# oscyloskop-0v2.net
KiCad netlist of a schematic drawn in EAGLE
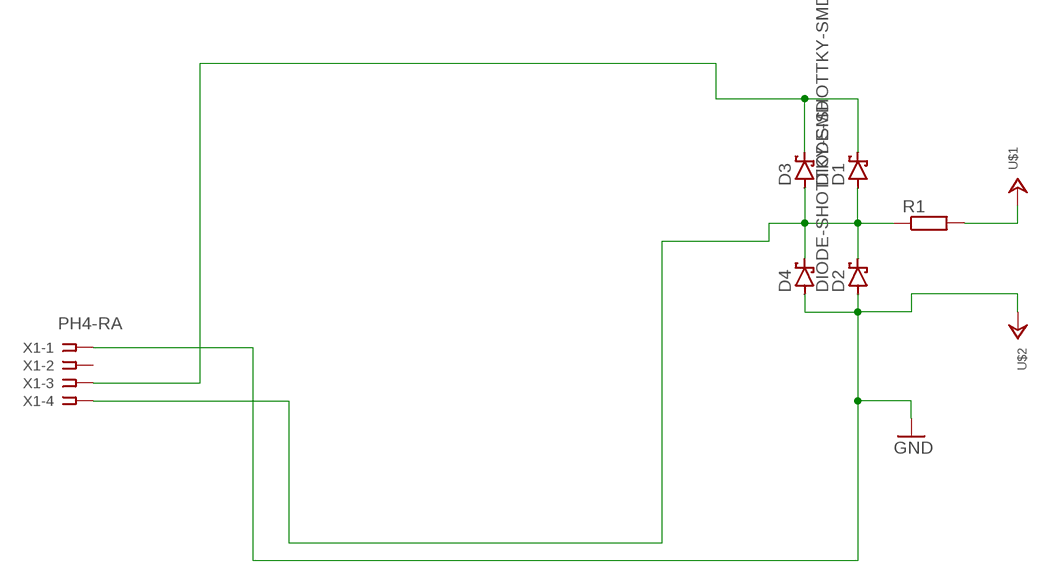
[diagram p0: schematic, sheet 1]

(export (version "E")
  (design (tool "Eeschema 10.0.6"))
  (components
    (comp (ref "D1")
      (value "DIODE-SHOTTKY-THT")
      (footprint "eagle-import:DO41-7.6")
      (libsource (lib "eagle-import") (part "DIODE-SHOTTKY-THT"))
    )
    (comp (ref "D2")
      (value "DIODE-SHOTTKY-THT")
      (footprint "eagle-import:DO41-7.6")
      (libsource (lib "eagle-import") (part "DIODE-SHOTTKY-THT"))
    )
    (comp (ref "D3")
      (value "DIODE-SHOTTKY-SMD")
      (footprint "eagle-import:SOD123")
      (libsource (lib "eagle-import") (part "DIODE-SHOTTKY-SMD"))
    )
    (comp (ref "D4")
      (value "DIODE-SHOTTKY-SMD")
      (footprint "eagle-import:SOD123")
      (libsource (lib "eagle-import") (part "DIODE-SHOTTKY-SMD"))
    )
    (comp (ref "R1")
      (value "R0204/7")
      (footprint "eagle-import:0204_7")
      (libsource (lib "eagle-import") (part "R0204/7"))
    )
    (comp (ref "U$1")
      (value "CON-BANANA")
      (footprint "eagle-import:BANANA")
      (libsource (lib "eagle-import") (part "CON-BANANA"))
    )
    (comp (ref "U$2")
      (value "CON-BANANA")
      (footprint "eagle-import:BANANA")
      (libsource (lib "eagle-import") (part "CON-BANANA"))
    )
    (comp (ref "X1")
      (value "PH4-RA")
      (footprint "eagle-import:SSW-104-02-G-S-RA")
      (fields (field (name "MF") "Samtec Inc.") (field (name "MPN") "SSW-104-02-G-S-RA"))
      (libsource (lib "eagle-import") (part "PH4-RA"))
    )
  )
  (nets
    (net (code "1") (name "GND") (class "Default")
      (node (ref "D2") (pin "A") (pinfunction "A_A") (pintype "passive"))
      (node (ref "D4") (pin "A") (pinfunction "A_A") (pintype "passive"))
      (node (ref "U$2") (pin "P$1") (pinfunction "IO_P$1") (pintype "output"))
      (node (ref "X1") (pin "1") (pinfunction "1_1") (pintype "passive"))
    )
    (net (code "2") (name "Net-(U$1-IO)") (class "Default")
      (node (ref "R1") (pin "2") (pinfunction "2_2") (pintype "passive"))
      (node (ref "U$1") (pin "P$1") (pinfunction "IO_P$1") (pintype "output"))
    )
    (net (code "3") (name "Net-(X1C-1)") (class "Default")
      (node (ref "D1") (pin "C") (pinfunction "C_C") (pintype "passive"))
      (node (ref "D3") (pin "C") (pinfunction "C_C") (pintype "passive"))
      (node (ref "X1") (pin "3") (pinfunction "1_3") (pintype "passive"))
    )
    (net (code "4") (name "Net-(X1D-1)") (class "Default")
      (node (ref "D1") (pin "A") (pinfunction "A_A") (pintype "passive"))
      (node (ref "D2") (pin "C") (pinfunction "C_C") (pintype "passive"))
      (node (ref "D3") (pin "A") (pinfunction "A_A") (pintype "passive"))
      (node (ref "D4") (pin "C") (pinfunction "C_C") (pintype "passive"))
      (node (ref "R1") (pin "1") (pinfunction "1_1") (pintype "passive"))
      (node (ref "X1") (pin "4") (pinfunction "1_4") (pintype "passive"))
    )
    (net (code "5") (name "unconnected-(X1B-1-Pad2)") (class "Default")
      (node (ref "X1") (pin "2") (pinfunction "1_2") (pintype "passive"))
    )
  )
)
